# MicroMod-RP2040-ProcessorBoard.net
KiCad netlist of a schematic drawn in EAGLE
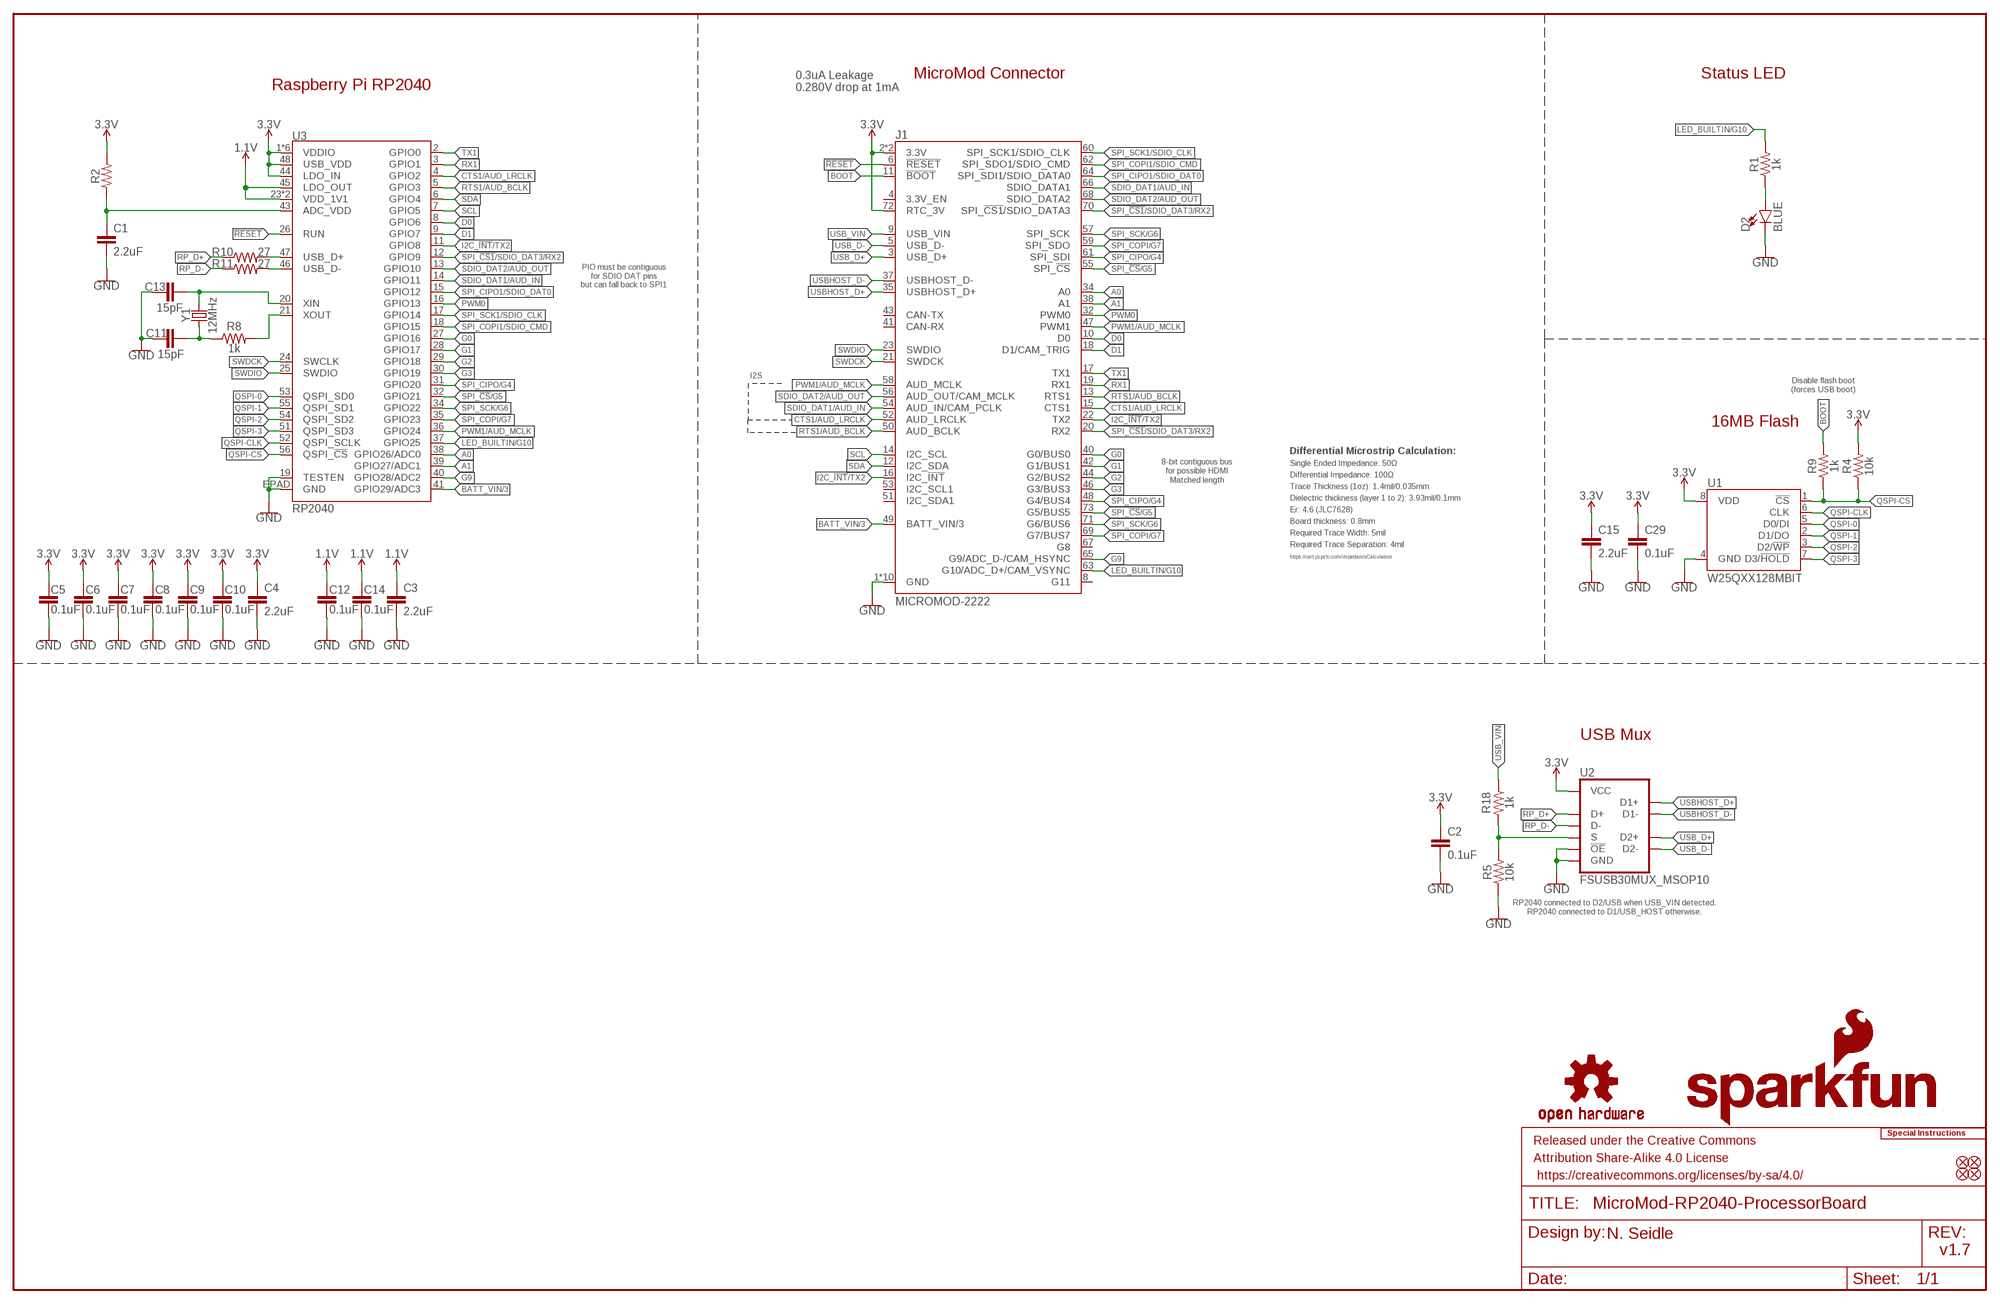
[diagram p0: schematic, sheet 1]

(export (version "E")
  (design (tool "Eeschema 10.0.6"))
  (components
    (comp (ref "C1")
      (value "2.2uF")
      (footprint "eagle-import:0402-TIGHT")
      (libsource (lib "eagle-import") (part "2.2UF-0402_TIGHT-10V-10%-X5R"))
    )
    (comp (ref "C2")
      (value "0.1uF")
      (footprint "eagle-import:0402-TIGHT")
      (libsource (lib "eagle-import") (part "0.1UF-0402T-6.3V-10%-X7R"))
    )
    (comp (ref "C3")
      (value "2.2uF")
      (footprint "eagle-import:0402-TIGHT")
      (libsource (lib "eagle-import") (part "2.2UF-0402_TIGHT-10V-10%-X5R"))
    )
    (comp (ref "C4")
      (value "2.2uF")
      (footprint "eagle-import:0402-TIGHT")
      (libsource (lib "eagle-import") (part "2.2UF-0402_TIGHT-10V-10%-X5R"))
    )
    (comp (ref "C5")
      (value "0.1uF")
      (footprint "eagle-import:0402-TIGHT")
      (libsource (lib "eagle-import") (part "0.1UF-0402T-6.3V-10%-X7R"))
    )
    (comp (ref "C6")
      (value "0.1uF")
      (footprint "eagle-import:0402-TIGHT")
      (libsource (lib "eagle-import") (part "0.1UF-0402T-6.3V-10%-X7R"))
    )
    (comp (ref "C7")
      (value "0.1uF")
      (footprint "eagle-import:0402-TIGHT")
      (libsource (lib "eagle-import") (part "0.1UF-0402T-6.3V-10%-X7R"))
    )
    (comp (ref "C8")
      (value "0.1uF")
      (footprint "eagle-import:0402-TIGHT")
      (libsource (lib "eagle-import") (part "0.1UF-0402T-6.3V-10%-X7R"))
    )
    (comp (ref "C9")
      (value "0.1uF")
      (footprint "eagle-import:0402-TIGHT")
      (libsource (lib "eagle-import") (part "0.1UF-0402T-6.3V-10%-X7R"))
    )
    (comp (ref "C10")
      (value "0.1uF")
      (footprint "eagle-import:0402-TIGHT")
      (libsource (lib "eagle-import") (part "0.1UF-0402T-6.3V-10%-X7R"))
    )
    (comp (ref "C11")
      (value "15pF")
      (footprint "eagle-import:0402-TIGHT")
      (libsource (lib "eagle-import") (part "15PF-0402T-50V-5%"))
    )
    (comp (ref "C12")
      (value "0.1uF")
      (footprint "eagle-import:0402-TIGHT")
      (libsource (lib "eagle-import") (part "0.1UF-0402T-6.3V-10%-X7R"))
    )
    (comp (ref "C13")
      (value "15pF")
      (footprint "eagle-import:0402-TIGHT")
      (libsource (lib "eagle-import") (part "15PF-0402T-50V-5%"))
    )
    (comp (ref "C14")
      (value "0.1uF")
      (footprint "eagle-import:0402-TIGHT")
      (libsource (lib "eagle-import") (part "0.1UF-0402T-6.3V-10%-X7R"))
    )
    (comp (ref "C15")
      (value "2.2uF")
      (footprint "eagle-import:0402-TIGHT")
      (libsource (lib "eagle-import") (part "2.2UF-0402_TIGHT-10V-10%-X5R"))
    )
    (comp (ref "C29")
      (value "0.1uF")
      (footprint "eagle-import:0402-TIGHT")
      (libsource (lib "eagle-import") (part "0.1UF-0402T-6.3V-10%-X7R"))
    )
    (comp (ref "D2")
      (value "BLUE")
      (footprint "eagle-import:LED-0603")
      (libsource (lib "eagle-import") (part "LED-BLUE0603"))
    )
    (comp (ref "FD1")
      (value "FIDUCIALUFIDUCIAL")
      (footprint "eagle-import:FIDUCIAL-MICRO")
      (libsource (lib "eagle-import") (part "FIDUCIALUFIDUCIAL"))
    )
    (comp (ref "FD2")
      (value "FIDUCIALUFIDUCIAL")
      (footprint "eagle-import:FIDUCIAL-MICRO")
      (libsource (lib "eagle-import") (part "FIDUCIALUFIDUCIAL"))
    )
    (comp (ref "FD3")
      (value "FIDUCIALUFIDUCIAL")
      (footprint "eagle-import:FIDUCIAL-MICRO")
      (libsource (lib "eagle-import") (part "FIDUCIALUFIDUCIAL"))
    )
    (comp (ref "FD4")
      (value "FIDUCIALUFIDUCIAL")
      (footprint "eagle-import:FIDUCIAL-MICRO")
      (libsource (lib "eagle-import") (part "FIDUCIALUFIDUCIAL"))
    )
    (comp (ref "FRAME1")
      (value "FRAME-LEDGER")
      (footprint "eagle-import:CREATIVE_COMMONS")
      (libsource (lib "eagle-import") (part "FRAME-LEDGER"))
    )
    (comp (ref "J1")
      (value "MICROMOD-2222")
      (footprint "eagle-import:M.2-CARD-E-22")
      (libsource (lib "eagle-import") (part "MICROMOD-2222"))
    )
    (comp (ref "LOGO1")
      (value "SFE_LOGO_NAME_FLAME.1_INCH")
      (footprint "eagle-import:SFE_LOGO_NAME_FLAME_.1")
      (libsource (lib "eagle-import") (part "SFE_LOGO_NAME_FLAME.1_INCH"))
    )
    (comp (ref "LOGO2")
      (value "SFE_LOGO_FLAME.1_INCH")
      (footprint "eagle-import:SFE_LOGO_FLAME_.1")
      (libsource (lib "eagle-import") (part "SFE_LOGO_FLAME.1_INCH"))
    )
    (comp (ref "LOGO3")
      (value "OSHW-LOGOMINI")
      (footprint "eagle-import:OSHW-LOGO-MINI")
      (libsource (lib "eagle-import") (part "OSHW-LOGOMINI"))
    )
    (comp (ref "LOGO4")
      (value "SPECIAL_INSTRUCTIONS-ORDERING")
      (footprint "eagle-import:ORDERING_INSTRUCTIONS")
      (libsource (lib "eagle-import") (part "SPECIAL_INSTRUCTIONS-ORDERING"))
    )
    (comp (ref "R1")
      (value "1k")
      (footprint "eagle-import:0402-TIGHT")
      (libsource (lib "eagle-import") (part "1KOHM-0402T-1/16W-1%"))
    )
    (comp (ref "R2")
      (value "200OHM-0402T-1/16W-1%")
      (footprint "eagle-import:0402-TIGHT")
      (libsource (lib "eagle-import") (part "200OHM-0402T-1/16W-1%"))
    )
    (comp (ref "R4")
      (value "10k")
      (footprint "eagle-import:0402-TIGHT")
      (libsource (lib "eagle-import") (part "10KOHM-0402T-1/16W-1%"))
    )
    (comp (ref "R5")
      (value "10k")
      (footprint "eagle-import:0402-TIGHT")
      (libsource (lib "eagle-import") (part "10KOHM-0402T-1/16W-1%"))
    )
    (comp (ref "R8")
      (value "1k")
      (footprint "eagle-import:0402-TIGHT")
      (libsource (lib "eagle-import") (part "1KOHM-0402T-1/16W-1%"))
    )
    (comp (ref "R9")
      (value "1k")
      (footprint "eagle-import:0402-TIGHT")
      (libsource (lib "eagle-import") (part "1KOHM-0402T-1/16W-1%"))
    )
    (comp (ref "R10")
      (value "27")
      (footprint "eagle-import:0402-TIGHT")
      (libsource (lib "eagle-import") (part "27OHM"))
    )
    (comp (ref "R11")
      (value "27")
      (footprint "eagle-import:0402-TIGHT")
      (libsource (lib "eagle-import") (part "27OHM"))
    )
    (comp (ref "R18")
      (value "1k")
      (footprint "eagle-import:0402-TIGHT")
      (libsource (lib "eagle-import") (part "1KOHM-0402T-1/16W-1%"))
    )
    (comp (ref "U1")
      (value "W25QXX128MBIT")
      (footprint "eagle-import:WSON-8-6X5-SKINNY_CENTERPAD")
      (libsource (lib "eagle-import") (part "W25QXX128MBIT-6X5-SKINNY_CENTER"))
    )
    (comp (ref "U2")
      (value "FSUSB30MUX_MSOP10")
      (footprint "eagle-import:MSOP10")
      (libsource (lib "eagle-import") (part "FSUSB30MUX_MSOP10"))
    )
    (comp (ref "U3")
      (value "RP2040")
      (footprint "eagle-import:QFN-56")
      (libsource (lib "eagle-import") (part "RP2040"))
    )
    (comp (ref "Y1")
      (value "12MHz")
      (footprint "eagle-import:CRYSTAL-SMD-2X2.5MM")
      (libsource (lib "eagle-import") (part "CRYSTAL-12MHZ"))
    )
  )
  (nets
    (net (code "1") (name "/I2C_~{INT}{slash}TX2") (class "Default")
      (node (ref "J1") (pin "16") (pinfunction "I2C_~{INT}_16") (pintype "bidirectional"))
      (node (ref "J1") (pin "22") (pinfunction "TX2_22") (pintype "bidirectional"))
      (node (ref "U3") (pin "11") (pinfunction "GPIO8_11") (pintype "bidirectional"))
    )
    (net (code "2") (name "/SPI_~{CS1}{slash}SDIO_DAT3{slash}RX2") (class "Default")
      (node (ref "J1") (pin "20") (pinfunction "RX2_20") (pintype "bidirectional"))
      (node (ref "J1") (pin "70") (pinfunction "SPI_~{CS1}/SDIO_DATA3_70") (pintype "bidirectional"))
      (node (ref "U3") (pin "12") (pinfunction "GPIO9_12") (pintype "bidirectional"))
    )
    (net (code "3") (name "/SPI_~{CS}{slash}G5") (class "Default")
      (node (ref "J1") (pin "55") (pinfunction "SPI_~{CS}_55") (pintype "bidirectional"))
      (node (ref "J1") (pin "73") (pinfunction "G5/BUS5_73") (pintype "bidirectional"))
      (node (ref "U3") (pin "32") (pinfunction "GPIO21_32") (pintype "bidirectional"))
    )
    (net (code "4") (name "/~{RESET}") (class "Default")
      (node (ref "J1") (pin "6") (pinfunction "~{RESET}_6") (pintype "bidirectional"))
      (node (ref "U3") (pin "26") (pinfunction "RUN_26") (pintype "bidirectional"))
    )
    (net (code "5") (name "1.1V") (class "Default")
      (node (ref "C12") (pin "1") (pinfunction "1_1") (pintype "passive"))
      (node (ref "C14") (pin "1") (pinfunction "1_1") (pintype "passive"))
      (node (ref "C3") (pin "1") (pinfunction "1_1") (pintype "passive"))
      (node (ref "U3") (pin "23") (pinfunction "VDD_1V1_23") (pintype "bidirectional"))
      (node (ref "U3") (pin "45") (pinfunction "LDO_OUT_45") (pintype "bidirectional"))
      (node (ref "U3") (pin "50") (pinfunction "VDD_1V1_50") (pintype "bidirectional"))
    )
    (net (code "6") (name "3.3V") (class "Default")
      (node (ref "C10") (pin "1") (pinfunction "1_1") (pintype "passive"))
      (node (ref "C15") (pin "1") (pinfunction "1_1") (pintype "passive"))
      (node (ref "C2") (pin "1") (pinfunction "1_1") (pintype "passive"))
      (node (ref "C29") (pin "1") (pinfunction "1_1") (pintype "passive"))
      (node (ref "C4") (pin "1") (pinfunction "1_1") (pintype "passive"))
      (node (ref "C5") (pin "1") (pinfunction "1_1") (pintype "passive"))
      (node (ref "C6") (pin "1") (pinfunction "1_1") (pintype "passive"))
      (node (ref "C7") (pin "1") (pinfunction "1_1") (pintype "passive"))
      (node (ref "C8") (pin "1") (pinfunction "1_1") (pintype "passive"))
      (node (ref "C9") (pin "1") (pinfunction "1_1") (pintype "passive"))
      (node (ref "J1") (pin "2") (pinfunction "3.3V_2") (pintype "bidirectional"))
      (node (ref "J1") (pin "72") (pinfunction "RTC_3V_72") (pintype "bidirectional"))
      (node (ref "J1") (pin "74") (pinfunction "3.3V_74") (pintype "bidirectional"))
      (node (ref "R2") (pin "2") (pinfunction "2_2") (pintype "passive"))
      (node (ref "R4") (pin "2") (pinfunction "2_2") (pintype "passive"))
      (node (ref "U1") (pin "8") (pinfunction "VDD_8") (pintype "bidirectional"))
      (node (ref "U2") (pin "10") (pinfunction "VCC_10") (pintype "bidirectional"))
      (node (ref "U3") (pin "1") (pinfunction "VDDIO_1") (pintype "bidirectional"))
      (node (ref "U3") (pin "10") (pinfunction "VDDIO_10") (pintype "bidirectional"))
      (node (ref "U3") (pin "22") (pinfunction "VDDIO_22") (pintype "bidirectional"))
      (node (ref "U3") (pin "33") (pinfunction "VDDIO_33") (pintype "bidirectional"))
      (node (ref "U3") (pin "42") (pinfunction "VDDIO_42") (pintype "bidirectional"))
      (node (ref "U3") (pin "44") (pinfunction "LDO_IN_44") (pintype "bidirectional"))
      (node (ref "U3") (pin "48") (pinfunction "USB_VDD_48") (pintype "bidirectional"))
      (node (ref "U3") (pin "49") (pinfunction "VDDIO_49") (pintype "bidirectional"))
    )
    (net (code "7") (name "A0") (class "Default")
      (node (ref "J1") (pin "34") (pinfunction "A0_34") (pintype "bidirectional"))
      (node (ref "U3") (pin "38") (pinfunction "GPIO26/ADC0_38") (pintype "bidirectional"))
    )
    (net (code "8") (name "A1") (class "Default")
      (node (ref "J1") (pin "38") (pinfunction "A1_38") (pintype "bidirectional"))
      (node (ref "U3") (pin "39") (pinfunction "GPIO27/ADC1_39") (pintype "bidirectional"))
    )
    (net (code "9") (name "BATT_VIN{slash}3") (class "Default")
      (node (ref "J1") (pin "49") (pinfunction "BATT_VIN/3_49") (pintype "bidirectional"))
      (node (ref "U3") (pin "41") (pinfunction "GPIO29/ADC3_41") (pintype "bidirectional"))
    )
    (net (code "10") (name "BOOT") (class "Default")
      (node (ref "J1") (pin "11") (pinfunction "~{BOOT}_11") (pintype "bidirectional"))
      (node (ref "R9") (pin "2") (pinfunction "2_2") (pintype "passive"))
    )
    (net (code "11") (name "CTS1{slash}AUD_LRCLK") (class "Default")
      (node (ref "J1") (pin "15") (pinfunction "CTS1_15") (pintype "bidirectional"))
      (node (ref "J1") (pin "52") (pinfunction "AUD_LRCLK_52") (pintype "bidirectional"))
      (node (ref "U3") (pin "4") (pinfunction "GPIO2_4") (pintype "bidirectional"))
    )
    (net (code "12") (name "D0") (class "Default")
      (node (ref "J1") (pin "10") (pinfunction "D0_10") (pintype "bidirectional"))
      (node (ref "U3") (pin "8") (pinfunction "GPIO6_8") (pintype "bidirectional"))
    )
    (net (code "13") (name "D1") (class "Default")
      (node (ref "J1") (pin "18") (pinfunction "D1/CAM_TRIG_18") (pintype "bidirectional"))
      (node (ref "U3") (pin "9") (pinfunction "GPIO7_9") (pintype "bidirectional"))
    )
    (net (code "14") (name "G0") (class "Default")
      (node (ref "J1") (pin "40") (pinfunction "G0/BUS0_40") (pintype "bidirectional"))
      (node (ref "U3") (pin "27") (pinfunction "GPIO16_27") (pintype "bidirectional"))
    )
    (net (code "15") (name "G1") (class "Default")
      (node (ref "J1") (pin "42") (pinfunction "G1/BUS1_42") (pintype "bidirectional"))
      (node (ref "U3") (pin "28") (pinfunction "GPIO17_28") (pintype "bidirectional"))
    )
    (net (code "16") (name "G2") (class "Default")
      (node (ref "J1") (pin "44") (pinfunction "G2/BUS2_44") (pintype "bidirectional"))
      (node (ref "U3") (pin "29") (pinfunction "GPIO18_29") (pintype "bidirectional"))
    )
    (net (code "17") (name "G3") (class "Default")
      (node (ref "J1") (pin "46") (pinfunction "G3/BUS3_46") (pintype "bidirectional"))
      (node (ref "U3") (pin "30") (pinfunction "GPIO19_30") (pintype "bidirectional"))
    )
    (net (code "18") (name "G9") (class "Default")
      (node (ref "J1") (pin "65") (pinfunction "G9/ADC_D-/CAM_HSYNC_65") (pintype "bidirectional"))
      (node (ref "U3") (pin "40") (pinfunction "GPIO28/ADC2_40") (pintype "bidirectional"))
    )
    (net (code "19") (name "GND") (class "Default")
      (node (ref "C1") (pin "2") (pinfunction "2_2") (pintype "passive"))
      (node (ref "C10") (pin "2") (pinfunction "2_2") (pintype "passive"))
      (node (ref "C11") (pin "1") (pinfunction "1_1") (pintype "passive"))
      (node (ref "C12") (pin "2") (pinfunction "2_2") (pintype "passive"))
      (node (ref "C13") (pin "1") (pinfunction "1_1") (pintype "passive"))
      (node (ref "C14") (pin "2") (pinfunction "2_2") (pintype "passive"))
      (node (ref "C15") (pin "2") (pinfunction "2_2") (pintype "passive"))
      (node (ref "C2") (pin "2") (pinfunction "2_2") (pintype "passive"))
      (node (ref "C29") (pin "2") (pinfunction "2_2") (pintype "passive"))
      (node (ref "C3") (pin "2") (pinfunction "2_2") (pintype "passive"))
      (node (ref "C4") (pin "2") (pinfunction "2_2") (pintype "passive"))
      (node (ref "C5") (pin "2") (pinfunction "2_2") (pintype "passive"))
      (node (ref "C6") (pin "2") (pinfunction "2_2") (pintype "passive"))
      (node (ref "C7") (pin "2") (pinfunction "2_2") (pintype "passive"))
      (node (ref "C8") (pin "2") (pinfunction "2_2") (pintype "passive"))
      (node (ref "C9") (pin "2") (pinfunction "2_2") (pintype "passive"))
      (node (ref "D2") (pin "C") (pinfunction "C_C") (pintype "passive"))
      (node (ref "J1") (pin "1") (pinfunction "GND_1") (pintype "bidirectional"))
      (node (ref "J1") (pin "33") (pinfunction "GND_33") (pintype "bidirectional"))
      (node (ref "J1") (pin "36") (pinfunction "GND_36") (pintype "bidirectional"))
      (node (ref "J1") (pin "39") (pinfunction "GND_39") (pintype "bidirectional"))
      (node (ref "J1") (pin "45") (pinfunction "GND_45") (pintype "bidirectional"))
      (node (ref "J1") (pin "7") (pinfunction "GND_7") (pintype "bidirectional"))
      (node (ref "J1") (pin "75") (pinfunction "GND_75") (pintype "bidirectional"))
      (node (ref "J1") (pin "GND1") (pinfunction "GND_GND1") (pintype "bidirectional"))
      (node (ref "J1") (pin "GND2") (pinfunction "GND_GND2") (pintype "bidirectional"))
      (node (ref "J1") (pin "GND3") (pinfunction "GND_GND3") (pintype "bidirectional"))
      (node (ref "R5") (pin "1") (pinfunction "1_1") (pintype "passive"))
      (node (ref "U1") (pin "4") (pinfunction "GND_4") (pintype "bidirectional"))
      (node (ref "U2") (pin "5") (pinfunction "GND_5") (pintype "bidirectional"))
      (node (ref "U2") (pin "9") (pinfunction "~{OE}_9") (pintype "bidirectional"))
      (node (ref "U3") (pin "19") (pinfunction "TESTEN_19") (pintype "bidirectional"))
      (node (ref "U3") (pin "EPAD") (pinfunction "GND_EPAD") (pintype "bidirectional"))
    )
    (net (code "20") (name "LED_BUILTIN{slash}G10") (class "Default")
      (node (ref "J1") (pin "63") (pinfunction "G10/ADC_D+/CAM_VSYNC_63") (pintype "bidirectional"))
      (node (ref "R1") (pin "2") (pinfunction "2_2") (pintype "passive"))
      (node (ref "U3") (pin "37") (pinfunction "GPIO25_37") (pintype "bidirectional"))
    )
    (net (code "21") (name "Net-(D2-PadA)") (class "Default")
      (node (ref "D2") (pin "A") (pinfunction "A_A") (pintype "passive"))
      (node (ref "R1") (pin "1") (pinfunction "1_1") (pintype "passive"))
    )
    (net (code "22") (name "Net-(U2-S)") (class "Default")
      (node (ref "R18") (pin "2") (pinfunction "2_2") (pintype "passive"))
      (node (ref "R5") (pin "2") (pinfunction "2_2") (pintype "passive"))
      (node (ref "U2") (pin "1") (pinfunction "S_1") (pintype "bidirectional"))
    )
    (net (code "23") (name "Net-(U3-ADC_VDD)") (class "Default")
      (node (ref "C1") (pin "1") (pinfunction "1_1") (pintype "passive"))
      (node (ref "R2") (pin "1") (pinfunction "1_1") (pintype "passive"))
      (node (ref "U3") (pin "43") (pinfunction "ADC_VDD_43") (pintype "bidirectional"))
    )
    (net (code "24") (name "Net-(U3-USB_D+)") (class "Default")
      (node (ref "R10") (pin "2") (pinfunction "2_2") (pintype "passive"))
      (node (ref "U3") (pin "47") (pinfunction "USB_D+_47") (pintype "bidirectional"))
    )
    (net (code "25") (name "Net-(U3-USB_D-)") (class "Default")
      (node (ref "R11") (pin "2") (pinfunction "2_2") (pintype "passive"))
      (node (ref "U3") (pin "46") (pinfunction "USB_D-_46") (pintype "bidirectional"))
    )
    (net (code "26") (name "Net-(U3-XIN)") (class "Default")
      (node (ref "C13") (pin "2") (pinfunction "2_2") (pintype "passive"))
      (node (ref "U3") (pin "20") (pinfunction "XIN_20") (pintype "bidirectional"))
      (node (ref "Y1") (pin "P3") (pinfunction "2_P3") (pintype "passive"))
    )
    (net (code "27") (name "Net-(U3-XOUT)") (class "Default")
      (node (ref "R8") (pin "2") (pinfunction "2_2") (pintype "passive"))
      (node (ref "U3") (pin "21") (pinfunction "XOUT_21") (pintype "bidirectional"))
    )
    (net (code "28") (name "Net-(Y1-1)") (class "Default")
      (node (ref "C11") (pin "2") (pinfunction "2_2") (pintype "passive"))
      (node (ref "R8") (pin "1") (pinfunction "1_1") (pintype "passive"))
      (node (ref "Y1") (pin "P1") (pinfunction "1_P1") (pintype "passive"))
    )
    (net (code "29") (name "PWM0") (class "Default")
      (node (ref "J1") (pin "32") (pinfunction "PWM0_32") (pintype "bidirectional"))
      (node (ref "U3") (pin "16") (pinfunction "GPIO13_16") (pintype "bidirectional"))
    )
    (net (code "30") (name "PWM1{slash}AUD_MCLK") (class "Default")
      (node (ref "J1") (pin "47") (pinfunction "PWM1_47") (pintype "bidirectional"))
      (node (ref "J1") (pin "58") (pinfunction "AUD_MCLK_58") (pintype "bidirectional"))
      (node (ref "U3") (pin "36") (pinfunction "GPIO24_36") (pintype "bidirectional"))
    )
    (net (code "31") (name "QSPI-0") (class "Default")
      (node (ref "U1") (pin "5") (pinfunction "D0/DI_5") (pintype "bidirectional"))
      (node (ref "U3") (pin "53") (pinfunction "QSPI_SD0_53") (pintype "bidirectional"))
    )
    (net (code "32") (name "QSPI-1") (class "Default")
      (node (ref "U1") (pin "2") (pinfunction "D1/DO_2") (pintype "bidirectional"))
      (node (ref "U3") (pin "55") (pinfunction "QSPI_SD1_55") (pintype "bidirectional"))
    )
    (net (code "33") (name "QSPI-2") (class "Default")
      (node (ref "U1") (pin "3") (pinfunction "D2/~{WP}_3") (pintype "bidirectional"))
      (node (ref "U3") (pin "54") (pinfunction "QSPI_SD2_54") (pintype "bidirectional"))
    )
    (net (code "34") (name "QSPI-3") (class "Default")
      (node (ref "U1") (pin "7") (pinfunction "D3/~{HOLD}_7") (pintype "bidirectional"))
      (node (ref "U3") (pin "51") (pinfunction "QSPI_SD3_51") (pintype "bidirectional"))
    )
    (net (code "35") (name "QSPI-CLK") (class "Default")
      (node (ref "U1") (pin "6") (pinfunction "CLK_6") (pintype "bidirectional"))
      (node (ref "U3") (pin "52") (pinfunction "QSPI_SCLK_52") (pintype "bidirectional"))
    )
    (net (code "36") (name "QSPI-CS") (class "Default")
      (node (ref "R4") (pin "1") (pinfunction "1_1") (pintype "passive"))
      (node (ref "R9") (pin "1") (pinfunction "1_1") (pintype "passive"))
      (node (ref "U1") (pin "1") (pinfunction "~{CS}_1") (pintype "bidirectional"))
      (node (ref "U3") (pin "56") (pinfunction "QSPI_~{CS}_56") (pintype "bidirectional"))
    )
    (net (code "37") (name "RP_D+") (class "Default")
      (node (ref "R10") (pin "1") (pinfunction "1_1") (pintype "passive"))
      (node (ref "U2") (pin "4") (pinfunction "D+_4") (pintype "bidirectional"))
    )
    (net (code "38") (name "RP_D-") (class "Default")
      (node (ref "R11") (pin "1") (pinfunction "1_1") (pintype "passive"))
      (node (ref "U2") (pin "6") (pinfunction "D-_6") (pintype "bidirectional"))
    )
    (net (code "39") (name "RTS1{slash}AUD_BCLK") (class "Default")
      (node (ref "J1") (pin "13") (pinfunction "RTS1_13") (pintype "bidirectional"))
      (node (ref "J1") (pin "50") (pinfunction "AUD_BCLK_50") (pintype "bidirectional"))
      (node (ref "U3") (pin "5") (pinfunction "GPIO3_5") (pintype "bidirectional"))
    )
    (net (code "40") (name "RX1") (class "Default")
      (node (ref "J1") (pin "19") (pinfunction "RX1_19") (pintype "bidirectional"))
      (node (ref "U3") (pin "3") (pinfunction "GPIO1_3") (pintype "bidirectional"))
    )
    (net (code "41") (name "SCL") (class "Default")
      (node (ref "J1") (pin "14") (pinfunction "I2C_SCL_14") (pintype "bidirectional"))
      (node (ref "U3") (pin "7") (pinfunction "GPIO5_7") (pintype "bidirectional"))
    )
    (net (code "42") (name "SDA") (class "Default")
      (node (ref "J1") (pin "12") (pinfunction "I2C_SDA_12") (pintype "bidirectional"))
      (node (ref "U3") (pin "6") (pinfunction "GPIO4_6") (pintype "bidirectional"))
    )
    (net (code "43") (name "SDIO_DAT1{slash}AUD_IN") (class "Default")
      (node (ref "J1") (pin "54") (pinfunction "AUD_IN/CAM_PCLK_54") (pintype "bidirectional"))
      (node (ref "J1") (pin "66") (pinfunction "SDIO_DATA1_66") (pintype "bidirectional"))
      (node (ref "U3") (pin "14") (pinfunction "GPIO11_14") (pintype "bidirectional"))
    )
    (net (code "44") (name "SDIO_DAT2{slash}AUD_OUT") (class "Default")
      (node (ref "J1") (pin "56") (pinfunction "AUD_OUT/CAM_MCLK_56") (pintype "bidirectional"))
      (node (ref "J1") (pin "68") (pinfunction "SDIO_DATA2_68") (pintype "bidirectional"))
      (node (ref "U3") (pin "13") (pinfunction "GPIO10_13") (pintype "bidirectional"))
    )
    (net (code "45") (name "SPI_CIPO1{slash}SDIO_DAT0") (class "Default")
      (node (ref "J1") (pin "64") (pinfunction "SPI_SDI1/SDIO_DATA0_64") (pintype "bidirectional"))
      (node (ref "U3") (pin "15") (pinfunction "GPIO12_15") (pintype "bidirectional"))
    )
    (net (code "46") (name "SPI_CIPO{slash}G4") (class "Default")
      (node (ref "J1") (pin "48") (pinfunction "G4/BUS4_48") (pintype "bidirectional"))
      (node (ref "J1") (pin "61") (pinfunction "SPI_SDI_61") (pintype "bidirectional"))
      (node (ref "U3") (pin "31") (pinfunction "GPIO20_31") (pintype "bidirectional"))
    )
    (net (code "47") (name "SPI_COPI1{slash}SDIO_CMD") (class "Default")
      (node (ref "J1") (pin "62") (pinfunction "SPI_SDO1/SDIO_CMD_62") (pintype "bidirectional"))
      (node (ref "U3") (pin "18") (pinfunction "GPIO15_18") (pintype "bidirectional"))
    )
    (net (code "48") (name "SPI_COPI{slash}G7") (class "Default")
      (node (ref "J1") (pin "59") (pinfunction "SPI_SDO_59") (pintype "bidirectional"))
      (node (ref "J1") (pin "69") (pinfunction "G7/BUS7_69") (pintype "bidirectional"))
      (node (ref "U3") (pin "35") (pinfunction "GPIO23_35") (pintype "bidirectional"))
    )
    (net (code "49") (name "SPI_SCK1{slash}SDIO_CLK") (class "Default")
      (node (ref "J1") (pin "60") (pinfunction "SPI_SCK1/SDIO_CLK_60") (pintype "bidirectional"))
      (node (ref "U3") (pin "17") (pinfunction "GPIO14_17") (pintype "bidirectional"))
    )
    (net (code "50") (name "SPI_SCK{slash}G6") (class "Default")
      (node (ref "J1") (pin "57") (pinfunction "SPI_SCK_57") (pintype "bidirectional"))
      (node (ref "J1") (pin "71") (pinfunction "G6/BUS6_71") (pintype "bidirectional"))
      (node (ref "U3") (pin "34") (pinfunction "GPIO22_34") (pintype "bidirectional"))
    )
    (net (code "51") (name "SWDCK") (class "Default")
      (node (ref "J1") (pin "21") (pinfunction "SWDCK_21") (pintype "bidirectional"))
      (node (ref "U3") (pin "24") (pinfunction "SWCLK_24") (pintype "bidirectional"))
    )
    (net (code "52") (name "SWDIO") (class "Default")
      (node (ref "J1") (pin "23") (pinfunction "SWDIO_23") (pintype "bidirectional"))
      (node (ref "U3") (pin "25") (pinfunction "SWDIO_25") (pintype "bidirectional"))
    )
    (net (code "53") (name "TX1") (class "Default")
      (node (ref "J1") (pin "17") (pinfunction "TX1_17") (pintype "bidirectional"))
      (node (ref "U3") (pin "2") (pinfunction "GPIO0_2") (pintype "bidirectional"))
    )
    (net (code "54") (name "USBHOST_D+") (class "Default")
      (node (ref "J1") (pin "35") (pinfunction "USBHOST_D+_35") (pintype "bidirectional"))
      (node (ref "U2") (pin "2") (pinfunction "D1+_2") (pintype "bidirectional"))
    )
    (net (code "55") (name "USBHOST_D-") (class "Default")
      (node (ref "J1") (pin "37") (pinfunction "USBHOST_D-_37") (pintype "bidirectional"))
      (node (ref "U2") (pin "8") (pinfunction "D1-_8") (pintype "bidirectional"))
    )
    (net (code "56") (name "USB_D+") (class "Default")
      (node (ref "J1") (pin "3") (pinfunction "USB_D+_3") (pintype "bidirectional"))
      (node (ref "U2") (pin "3") (pinfunction "D2+_3") (pintype "bidirectional"))
    )
    (net (code "57") (name "USB_D-") (class "Default")
      (node (ref "J1") (pin "5") (pinfunction "USB_D-_5") (pintype "bidirectional"))
      (node (ref "U2") (pin "7") (pinfunction "D2-_7") (pintype "bidirectional"))
    )
    (net (code "58") (name "USB_VIN") (class "Default")
      (node (ref "J1") (pin "9") (pinfunction "USB_VIN_9") (pintype "bidirectional"))
      (node (ref "R18") (pin "1") (pinfunction "1_1") (pintype "passive"))
    )
    (net (code "59") (name "unconnected-(J1-3.3V_EN-Pad4)") (class "Default")
      (node (ref "J1") (pin "4") (pinfunction "3.3V_EN_4") (pintype "bidirectional"))
    )
    (net (code "60") (name "unconnected-(J1-CAN-RX-Pad41)") (class "Default")
      (node (ref "J1") (pin "41") (pinfunction "CAN-RX_41") (pintype "bidirectional"))
    )
    (net (code "61") (name "unconnected-(J1-CAN-TX-Pad43)") (class "Default")
      (node (ref "J1") (pin "43") (pinfunction "CAN-TX_43") (pintype "bidirectional"))
    )
    (net (code "62") (name "unconnected-(J1-G8-Pad67)") (class "Default")
      (node (ref "J1") (pin "67") (pinfunction "G8_67") (pintype "bidirectional"))
    )
    (net (code "63") (name "unconnected-(J1-G11-Pad8)") (class "Default")
      (node (ref "J1") (pin "8") (pinfunction "G11_8") (pintype "bidirectional"))
    )
    (net (code "64") (name "unconnected-(J1-I2C_SCL1-Pad53)") (class "Default")
      (node (ref "J1") (pin "53") (pinfunction "I2C_SCL1_53") (pintype "bidirectional"))
    )
    (net (code "65") (name "unconnected-(J1-I2C_SDA1-Pad51)") (class "Default")
      (node (ref "J1") (pin "51") (pinfunction "I2C_SDA1_51") (pintype "bidirectional"))
    )
  )
)
